# monitoring-sources-with-mbed-hw.net
KiCad netlist of a schematic drawn in Altium Designer
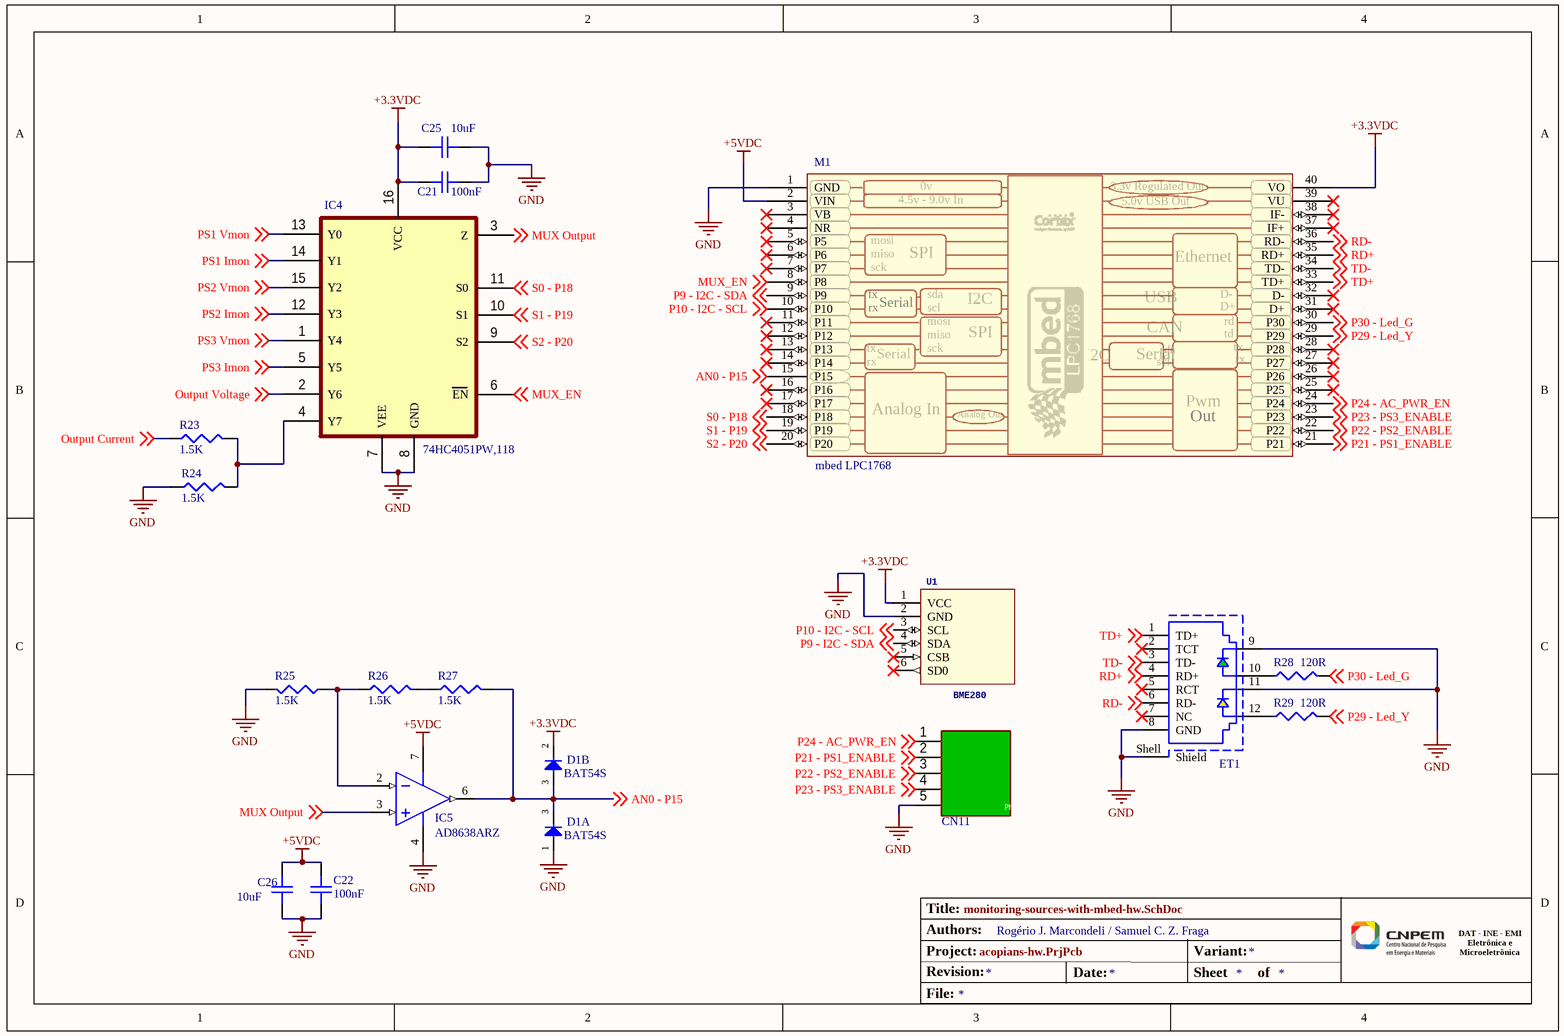
[diagram p0: monitoring-sources-with-mbed-hw.SchDoc]

(export (version "E")
  (design (tool "Eeschema 10.0.6"))
  (components
    (comp (ref "C21")
      (value "100nF")
      (footprint "C0805")
      (description "Capacitor 0.1UF 50V X7R 0805")
      (fields (field (name "TOLERANCE") "10%") (field (name "VOLTAGE") "50V"))
      (libsource (lib "acopians-monitoring-hw-library-schematic") (part "CAPACITOR 100nF/50V"))
    )
    (comp (ref "C22")
      (value "100nF")
      (footprint "C0805")
      (description "Capacitor 0.1UF 50V X7R 0805")
      (fields (field (name "TOLERANCE") "10%") (field (name "VOLTAGE") "50V"))
      (libsource (lib "acopians-monitoring-hw-library-schematic") (part "CAPACITOR 100nF/50V"))
    )
    (comp (ref "C25")
      (value "10uF")
      (footprint "C0805")
      (description "Capacitor 10UF 35V X5R 0805")
      (fields
        (field (name "MANUFACTURER") "TDK")
        (field (name "MANUFACTURER PART NUMBER") "C2012X5R1V106K085AC")
      )
      (libsource (lib "acopians-monitoring-hw-library-schematic") (part "CAPACITOR 10uF/35V"))
    )
    (comp (ref "C26")
      (value "10uF")
      (footprint "C0805")
      (description "Capacitor 10UF 35V X5R 0805")
      (fields
        (field (name "MANUFACTURER") "TDK")
        (field (name "MANUFACTURER PART NUMBER") "C2012X5R1V106K085AC")
      )
      (libsource (lib "acopians-monitoring-hw-library-schematic") (part "CAPACITOR 10uF/35V"))
    )
    (comp (ref "CN11")
      (value "1879311")
      (footprint "Conector Phoenix 5 vias 1879311")
      (description "Conector Phoenix 5 vias 1879311")
      (libsource (lib "acopians-monitoring-hw-library-schematic") (part "CONECTOR PHOENIX 5 VIAS 1879311"))
    )
    (comp (ref "D1")
      (value "BAT54S")
      (footprint "SOT23-3")
      (description "200mA Schottky Diode, 30 VRRM, Cascade Configutation, SMD SOT-23")
      (fields (field (name "AUTHOR") "CERN DEM JLC"))
      (libsource (lib "acopians-monitoring-hw-library-schematic") (part "Diodo BAT54S"))
    )
    (comp (ref "ET1")
      (value "7499010121A")
      (footprint "7499010121A")
      (description "WE-RJ45 LAN Transformer, THT, 1 Port, 10/100 Base-T, Tab Up")
      (libsource (lib "acopians-monitoring-hw-library-schematic") (part "7499010121A"))
    )
    (comp (ref "IC4")
      (value "8-channel analog multiplexer, TSSOP-16")
      (footprint "TSSOP-16")
      (fields (field (name "MANUFACTURER PART NUMBER 1") "74HC4051PW,118"))
      (libsource (lib "acopians-monitoring-hw-library-schematic") (part "74HC4051PW,118"))
    )
    (comp (ref "IC5")
      (value "AD8638ARZ")
      (footprint "SOIC-N-8")
      (description "Precision Amplifiers 16V Auto-Zero CMOS Amplifier")
      (libsource (lib "acopians-monitoring-hw-library-schematic") (part "AD8638ARZ"))
    )
    (comp (ref "M1")
      (value "mbed LPC1768")
      (footprint "DIP40-LPC1768")
      (description "Mbed LPC 1768")
      (libsource (lib "acopians-monitoring-hw-library-schematic") (part "MBED LPC1768"))
    )
    (comp (ref "R23")
      (value "1.5K")
      (footprint "R0603")
      (description "Resistor SMD 1.5K OHM 0.1% 1/10W 0603")
      (fields (field (name "TOLERANCE") "0.1%"))
      (libsource (lib "acopians-monitoring-hw-library-schematic") (part "RESISTOR 1.5K"))
    )
    (comp (ref "R24")
      (value "1.5K")
      (footprint "R0603")
      (description "Resistor SMD 1.5K OHM 0.1% 1/10W 0603")
      (fields (field (name "TOLERANCE") "0.1%"))
      (libsource (lib "acopians-monitoring-hw-library-schematic") (part "RESISTOR 1.5K"))
    )
    (comp (ref "R25")
      (value "1.5K")
      (footprint "R0603")
      (description "Resistor SMD 1.5K OHM 0.1% 1/10W 0603")
      (fields (field (name "TOLERANCE") "0.1%"))
      (libsource (lib "acopians-monitoring-hw-library-schematic") (part "RESISTOR 1.5K"))
    )
    (comp (ref "R26")
      (value "1.5K")
      (footprint "R0603")
      (description "Resistor SMD 1.5K OHM 0.1% 1/10W 0603")
      (fields (field (name "TOLERANCE") "0.1%"))
      (libsource (lib "acopians-monitoring-hw-library-schematic") (part "RESISTOR 1.5K"))
    )
    (comp (ref "R27")
      (value "1.5K")
      (footprint "R0603")
      (description "Resistor SMD 1.5K OHM 0.1% 1/10W 0603")
      (fields (field (name "TOLERANCE") "0.1%"))
      (libsource (lib "acopians-monitoring-hw-library-schematic") (part "RESISTOR 1.5K"))
    )
    (comp (ref "R28")
      (value "120R")
      (footprint "R0805")
      (description "Resistor SMD 120R OHM 1% 1/8W 0805")
      (fields (field (name "TOLERANCE") "1%"))
      (libsource (lib "acopians-monitoring-hw-library-schematic") (part "RESISTOR 120R"))
    )
    (comp (ref "R29")
      (value "120R")
      (footprint "R0805")
      (description "Resistor SMD 120R OHM 1% 1/8W 0805")
      (fields (field (name "TOLERANCE") "1%"))
      (libsource (lib "acopians-monitoring-hw-library-schematic") (part "RESISTOR 120R"))
    )
    (comp (ref "U1")
      (value "BME280")
      (footprint "BME280")
      (libsource (lib "acopians-monitoring-hw-library-schematic") (part "BME280"))
    )
  )
  (nets
    (net (code "1") (name "+3.3VDC") (class "Default")
      (node (ref "C21") (pin "2") (pinfunction "2_2") (pintype "passive"))
      (node (ref "C25") (pin "1") (pinfunction "1_1") (pintype "passive"))
      (node (ref "D1") (pin "2") (pinfunction "C_2") (pintype "passive"))
      (node (ref "IC4") (pin "16") (pinfunction "VCC_16") (pintype "power_in"))
      (node (ref "M1") (pin "40") (pinfunction "VO_40") (pintype "power_in"))
      (node (ref "U1") (pin "1") (pinfunction "VCC_1") (pintype "power_in"))
    )
    (net (code "2") (name "+5VDC") (class "Default")
      (node (ref "C22") (pin "2") (pinfunction "2_2") (pintype "passive"))
      (node (ref "C26") (pin "1") (pinfunction "1_1") (pintype "passive"))
      (node (ref "IC5") (pin "7") (pinfunction "V+_7") (pintype "power_in"))
      (node (ref "M1") (pin "2") (pinfunction "VIN_2") (pintype "power_in"))
    )
    (net (code "3") (name "AN0 - P15") (class "Default")
      (node (ref "D1") (pin "3") (pinfunction "COMAC_3") (pintype "passive"))
      (node (ref "IC5") (pin "6") (pinfunction "Output_6") (pintype "output"))
      (node (ref "M1") (pin "15") (pinfunction "P15_15") (pintype "passive"))
      (node (ref "R27") (pin "2") (pinfunction "2_2") (pintype "passive"))
    )
    (net (code "4") (name "GND") (class "Default")
      (node (ref "C21") (pin "1") (pinfunction "1_1") (pintype "passive"))
      (node (ref "C22") (pin "1") (pinfunction "1_1") (pintype "passive"))
      (node (ref "C25") (pin "2") (pinfunction "2_2") (pintype "passive"))
      (node (ref "C26") (pin "2") (pinfunction "2_2") (pintype "passive"))
      (node (ref "CN11") (pin "5") (pinfunction "5_5") (pintype "passive"))
      (node (ref "D1") (pin "1") (pinfunction "A_1") (pintype "passive"))
      (node (ref "ET1") (pin "11") (pinfunction "KY_11") (pintype "passive"))
      (node (ref "ET1") (pin "8") (pinfunction "GND_8") (pintype "passive"))
      (node (ref "ET1") (pin "9") (pinfunction "KG_9") (pintype "passive"))
      (node (ref "ET1") (pin "Shell") (pinfunction "Shield_Shell") (pintype "passive"))
      (node (ref "IC4") (pin "7") (pinfunction "VEE_7") (pintype "passive"))
      (node (ref "IC4") (pin "8") (pinfunction "GND_8") (pintype "passive"))
      (node (ref "IC5") (pin "4") (pinfunction "V-_4") (pintype "power_in"))
      (node (ref "M1") (pin "1") (pinfunction "GND_1") (pintype "power_in"))
      (node (ref "R24") (pin "1") (pinfunction "1_1") (pintype "passive"))
      (node (ref "R25") (pin "2") (pinfunction "2_2") (pintype "passive"))
      (node (ref "U1") (pin "2") (pinfunction "GND_2") (pintype "power_in"))
    )
    (net (code "5") (name "MUX Output") (class "Default")
      (node (ref "IC4") (pin "3") (pinfunction "Z_3") (pintype "passive"))
      (node (ref "IC5") (pin "3") (pinfunction "+In_3") (pintype "input"))
    )
    (net (code "6") (name "MUX_EN") (class "Default")
      (node (ref "IC4") (pin "6") (pinfunction "EN_6") (pintype "passive"))
      (node (ref "M1") (pin "8") (pinfunction "P8_8") (pintype "bidirectional"))
    )
    (net (code "7") (name "Net-(ET1-AG)") (class "Default")
      (node (ref "ET1") (pin "10") (pinfunction "AG_10") (pintype "passive"))
      (node (ref "R28") (pin "1") (pinfunction "1_1") (pintype "passive"))
    )
    (net (code "8") (name "Net-(ET1-AY)") (class "Default")
      (node (ref "ET1") (pin "12") (pinfunction "AY_12") (pintype "passive"))
      (node (ref "R29") (pin "1") (pinfunction "1_1") (pintype "passive"))
    )
    (net (code "9") (name "Net-(IC4-Y7)") (class "Default")
      (node (ref "IC4") (pin "4") (pinfunction "Y7_4") (pintype "passive"))
      (node (ref "R23") (pin "2") (pinfunction "2_2") (pintype "passive"))
      (node (ref "R24") (pin "2") (pinfunction "2_2") (pintype "passive"))
    )
    (net (code "10") (name "Net-(IC5--In)") (class "Default")
      (node (ref "IC5") (pin "2") (pinfunction "-In_2") (pintype "input"))
      (node (ref "R25") (pin "1") (pinfunction "1_1") (pintype "passive"))
      (node (ref "R26") (pin "1") (pinfunction "1_1") (pintype "passive"))
    )
    (net (code "11") (name "Net-(R26-Pad2)") (class "Default")
      (node (ref "R26") (pin "2") (pinfunction "2_2") (pintype "passive"))
      (node (ref "R27") (pin "1") (pinfunction "1_1") (pintype "passive"))
    )
    (net (code "12") (name "Output Current") (class "Default")
      (node (ref "R23") (pin "1") (pinfunction "1_1") (pintype "passive"))
    )
    (net (code "13") (name "Output Voltage") (class "Default")
      (node (ref "IC4") (pin "2") (pinfunction "Y6_2") (pintype "passive"))
    )
    (net (code "14") (name "P9 - I2C - SDA") (class "Default")
      (node (ref "M1") (pin "9") (pinfunction "P9_9") (pintype "bidirectional"))
      (node (ref "U1") (pin "4") (pinfunction "SDA_4") (pintype "bidirectional"))
    )
    (net (code "15") (name "P10 - I2C - SCL") (class "Default")
      (node (ref "M1") (pin "10") (pinfunction "P10_10") (pintype "bidirectional"))
      (node (ref "U1") (pin "3") (pinfunction "SCL_3") (pintype "bidirectional"))
    )
    (net (code "16") (name "P21 - PS1_ENABLE") (class "Default")
      (node (ref "CN11") (pin "2") (pinfunction "2_2") (pintype "passive"))
      (node (ref "M1") (pin "21") (pinfunction "P21_21") (pintype "bidirectional"))
    )
    (net (code "17") (name "P22 - PS2_ENABLE") (class "Default")
      (node (ref "CN11") (pin "3") (pinfunction "3_3") (pintype "passive"))
      (node (ref "M1") (pin "22") (pinfunction "P22_22") (pintype "bidirectional"))
    )
    (net (code "18") (name "P23 - PS3_ENABLE") (class "Default")
      (node (ref "CN11") (pin "4") (pinfunction "4_4") (pintype "passive"))
      (node (ref "M1") (pin "23") (pinfunction "P23_23") (pintype "bidirectional"))
    )
    (net (code "19") (name "P24 - AC_PWR_EN") (class "Default")
      (node (ref "CN11") (pin "1") (pinfunction "1_1") (pintype "passive"))
      (node (ref "M1") (pin "24") (pinfunction "P24_24") (pintype "bidirectional"))
    )
    (net (code "20") (name "P29 - Led_Y") (class "Default")
      (node (ref "M1") (pin "29") (pinfunction "P29_29") (pintype "bidirectional"))
      (node (ref "R29") (pin "2") (pinfunction "2_2") (pintype "passive"))
    )
    (net (code "21") (name "P30 - Led_G") (class "Default")
      (node (ref "M1") (pin "30") (pinfunction "P30_30") (pintype "bidirectional"))
      (node (ref "R28") (pin "2") (pinfunction "2_2") (pintype "passive"))
    )
    (net (code "22") (name "PS1 Imon") (class "Default")
      (node (ref "IC4") (pin "14") (pinfunction "Y1_14") (pintype "passive"))
    )
    (net (code "23") (name "PS1 Vmon") (class "Default")
      (node (ref "IC4") (pin "13") (pinfunction "Y0_13") (pintype "passive"))
    )
    (net (code "24") (name "PS2 Imon") (class "Default")
      (node (ref "IC4") (pin "12") (pinfunction "Y3_12") (pintype "passive"))
    )
    (net (code "25") (name "PS2 Vmon") (class "Default")
      (node (ref "IC4") (pin "15") (pinfunction "Y2_15") (pintype "passive"))
    )
    (net (code "26") (name "PS3 Imon") (class "Default")
      (node (ref "IC4") (pin "5") (pinfunction "Y5_5") (pintype "passive"))
    )
    (net (code "27") (name "PS3 Vmon") (class "Default")
      (node (ref "IC4") (pin "1") (pinfunction "Y4_1") (pintype "passive"))
    )
    (net (code "28") (name "RD+") (class "Default")
      (node (ref "ET1") (pin "4") (pinfunction "RD+_4") (pintype "passive"))
      (node (ref "M1") (pin "35") (pinfunction "RD+_35") (pintype "bidirectional"))
    )
    (net (code "29") (name "RD-") (class "Default")
      (node (ref "ET1") (pin "6") (pinfunction "RD-_6") (pintype "passive"))
      (node (ref "M1") (pin "36") (pinfunction "RD-_36") (pintype "bidirectional"))
    )
    (net (code "30") (name "S0 - P18") (class "Default")
      (node (ref "IC4") (pin "11") (pinfunction "S0_11") (pintype "passive"))
      (node (ref "M1") (pin "18") (pinfunction "P18_18") (pintype "bidirectional"))
    )
    (net (code "31") (name "S1 - P19") (class "Default")
      (node (ref "IC4") (pin "10") (pinfunction "S1_10") (pintype "passive"))
      (node (ref "M1") (pin "19") (pinfunction "P19_19") (pintype "bidirectional"))
    )
    (net (code "32") (name "S2 - P20") (class "Default")
      (node (ref "IC4") (pin "9") (pinfunction "S2_9") (pintype "passive"))
      (node (ref "M1") (pin "20") (pinfunction "P20_20") (pintype "bidirectional"))
    )
    (net (code "33") (name "TD+") (class "Default")
      (node (ref "ET1") (pin "1") (pinfunction "TD+_1") (pintype "passive"))
      (node (ref "M1") (pin "33") (pinfunction "TD+_33") (pintype "bidirectional"))
    )
    (net (code "34") (name "TD-") (class "Default")
      (node (ref "ET1") (pin "3") (pinfunction "TD-_3") (pintype "passive"))
      (node (ref "M1") (pin "34") (pinfunction "TD-_34") (pintype "bidirectional"))
    )
    (net (code "35") (name "unconnected-(ET1-NC-Pad7)") (class "Default")
      (node (ref "ET1") (pin "7") (pinfunction "NC_7") (pintype "passive+no_connect"))
    )
    (net (code "36") (name "unconnected-(ET1-RCT-Pad5)") (class "Default")
      (node (ref "ET1") (pin "5") (pinfunction "RCT_5") (pintype "passive+no_connect"))
    )
    (net (code "37") (name "unconnected-(ET1-TCT-Pad2)") (class "Default")
      (node (ref "ET1") (pin "2") (pinfunction "TCT_2") (pintype "passive+no_connect"))
    )
    (net (code "38") (name "unconnected-(M1-D+-Pad31)") (class "Default")
      (node (ref "M1") (pin "31") (pinfunction "D+_31") (pintype "bidirectional+no_connect"))
    )
    (net (code "39") (name "unconnected-(M1-D--Pad32)") (class "Default")
      (node (ref "M1") (pin "32") (pinfunction "D-_32") (pintype "bidirectional+no_connect"))
    )
    (net (code "40") (name "unconnected-(M1-IF+-Pad37)") (class "Default")
      (node (ref "M1") (pin "37") (pinfunction "IF+_37") (pintype "bidirectional+no_connect"))
    )
    (net (code "41") (name "unconnected-(M1-IF--Pad38)") (class "Default")
      (node (ref "M1") (pin "38") (pinfunction "IF-_38") (pintype "bidirectional+no_connect"))
    )
    (net (code "42") (name "unconnected-(M1-NR-Pad4)") (class "Default")
      (node (ref "M1") (pin "4") (pinfunction "NR_4") (pintype "power_in+no_connect"))
    )
    (net (code "43") (name "unconnected-(M1-P5-Pad5)") (class "Default")
      (node (ref "M1") (pin "5") (pinfunction "P5_5") (pintype "bidirectional+no_connect"))
    )
    (net (code "44") (name "unconnected-(M1-P6-Pad6)") (class "Default")
      (node (ref "M1") (pin "6") (pinfunction "P6_6") (pintype "bidirectional+no_connect"))
    )
    (net (code "45") (name "unconnected-(M1-P7-Pad7)") (class "Default")
      (node (ref "M1") (pin "7") (pinfunction "P7_7") (pintype "bidirectional+no_connect"))
    )
    (net (code "46") (name "unconnected-(M1-P11-Pad11)") (class "Default")
      (node (ref "M1") (pin "11") (pinfunction "P11_11") (pintype "bidirectional+no_connect"))
    )
    (net (code "47") (name "unconnected-(M1-P12-Pad12)") (class "Default")
      (node (ref "M1") (pin "12") (pinfunction "P12_12") (pintype "bidirectional+no_connect"))
    )
    (net (code "48") (name "unconnected-(M1-P13-Pad13)") (class "Default")
      (node (ref "M1") (pin "13") (pinfunction "P13_13") (pintype "bidirectional+no_connect"))
    )
    (net (code "49") (name "unconnected-(M1-P14-Pad14)") (class "Default")
      (node (ref "M1") (pin "14") (pinfunction "P14_14") (pintype "bidirectional+no_connect"))
    )
    (net (code "50") (name "unconnected-(M1-P16-Pad16)") (class "Default")
      (node (ref "M1") (pin "16") (pinfunction "P16_16") (pintype "bidirectional+no_connect"))
    )
    (net (code "51") (name "unconnected-(M1-P17-Pad17)") (class "Default")
      (node (ref "M1") (pin "17") (pinfunction "P17_17") (pintype "bidirectional+no_connect"))
    )
    (net (code "52") (name "unconnected-(M1-P25-Pad25)") (class "Default")
      (node (ref "M1") (pin "25") (pinfunction "P25_25") (pintype "bidirectional+no_connect"))
    )
    (net (code "53") (name "unconnected-(M1-P26-Pad26)") (class "Default")
      (node (ref "M1") (pin "26") (pinfunction "P26_26") (pintype "bidirectional+no_connect"))
    )
    (net (code "54") (name "unconnected-(M1-P27-Pad27)") (class "Default")
      (node (ref "M1") (pin "27") (pinfunction "P27_27") (pintype "bidirectional+no_connect"))
    )
    (net (code "55") (name "unconnected-(M1-P28-Pad28)") (class "Default")
      (node (ref "M1") (pin "28") (pinfunction "P28_28") (pintype "bidirectional+no_connect"))
    )
    (net (code "56") (name "unconnected-(M1-VB-Pad3)") (class "Default")
      (node (ref "M1") (pin "3") (pinfunction "VB_3") (pintype "power_in+no_connect"))
    )
    (net (code "57") (name "unconnected-(M1-VU-Pad39)") (class "Default")
      (node (ref "M1") (pin "39") (pinfunction "VU_39") (pintype "power_in+no_connect"))
    )
    (net (code "58") (name "unconnected-(U1-CSB-Pad5)") (class "Default")
      (node (ref "U1") (pin "5") (pinfunction "CSB_5") (pintype "input+no_connect"))
    )
    (net (code "59") (name "unconnected-(U1-SD0-Pad6)") (class "Default")
      (node (ref "U1") (pin "6") (pinfunction "SD0_6") (pintype "output+no_connect"))
    )
  )
)
